# SCH_OpenRICE.net
KiCad netlist of a schematic drawn in EasyEDA
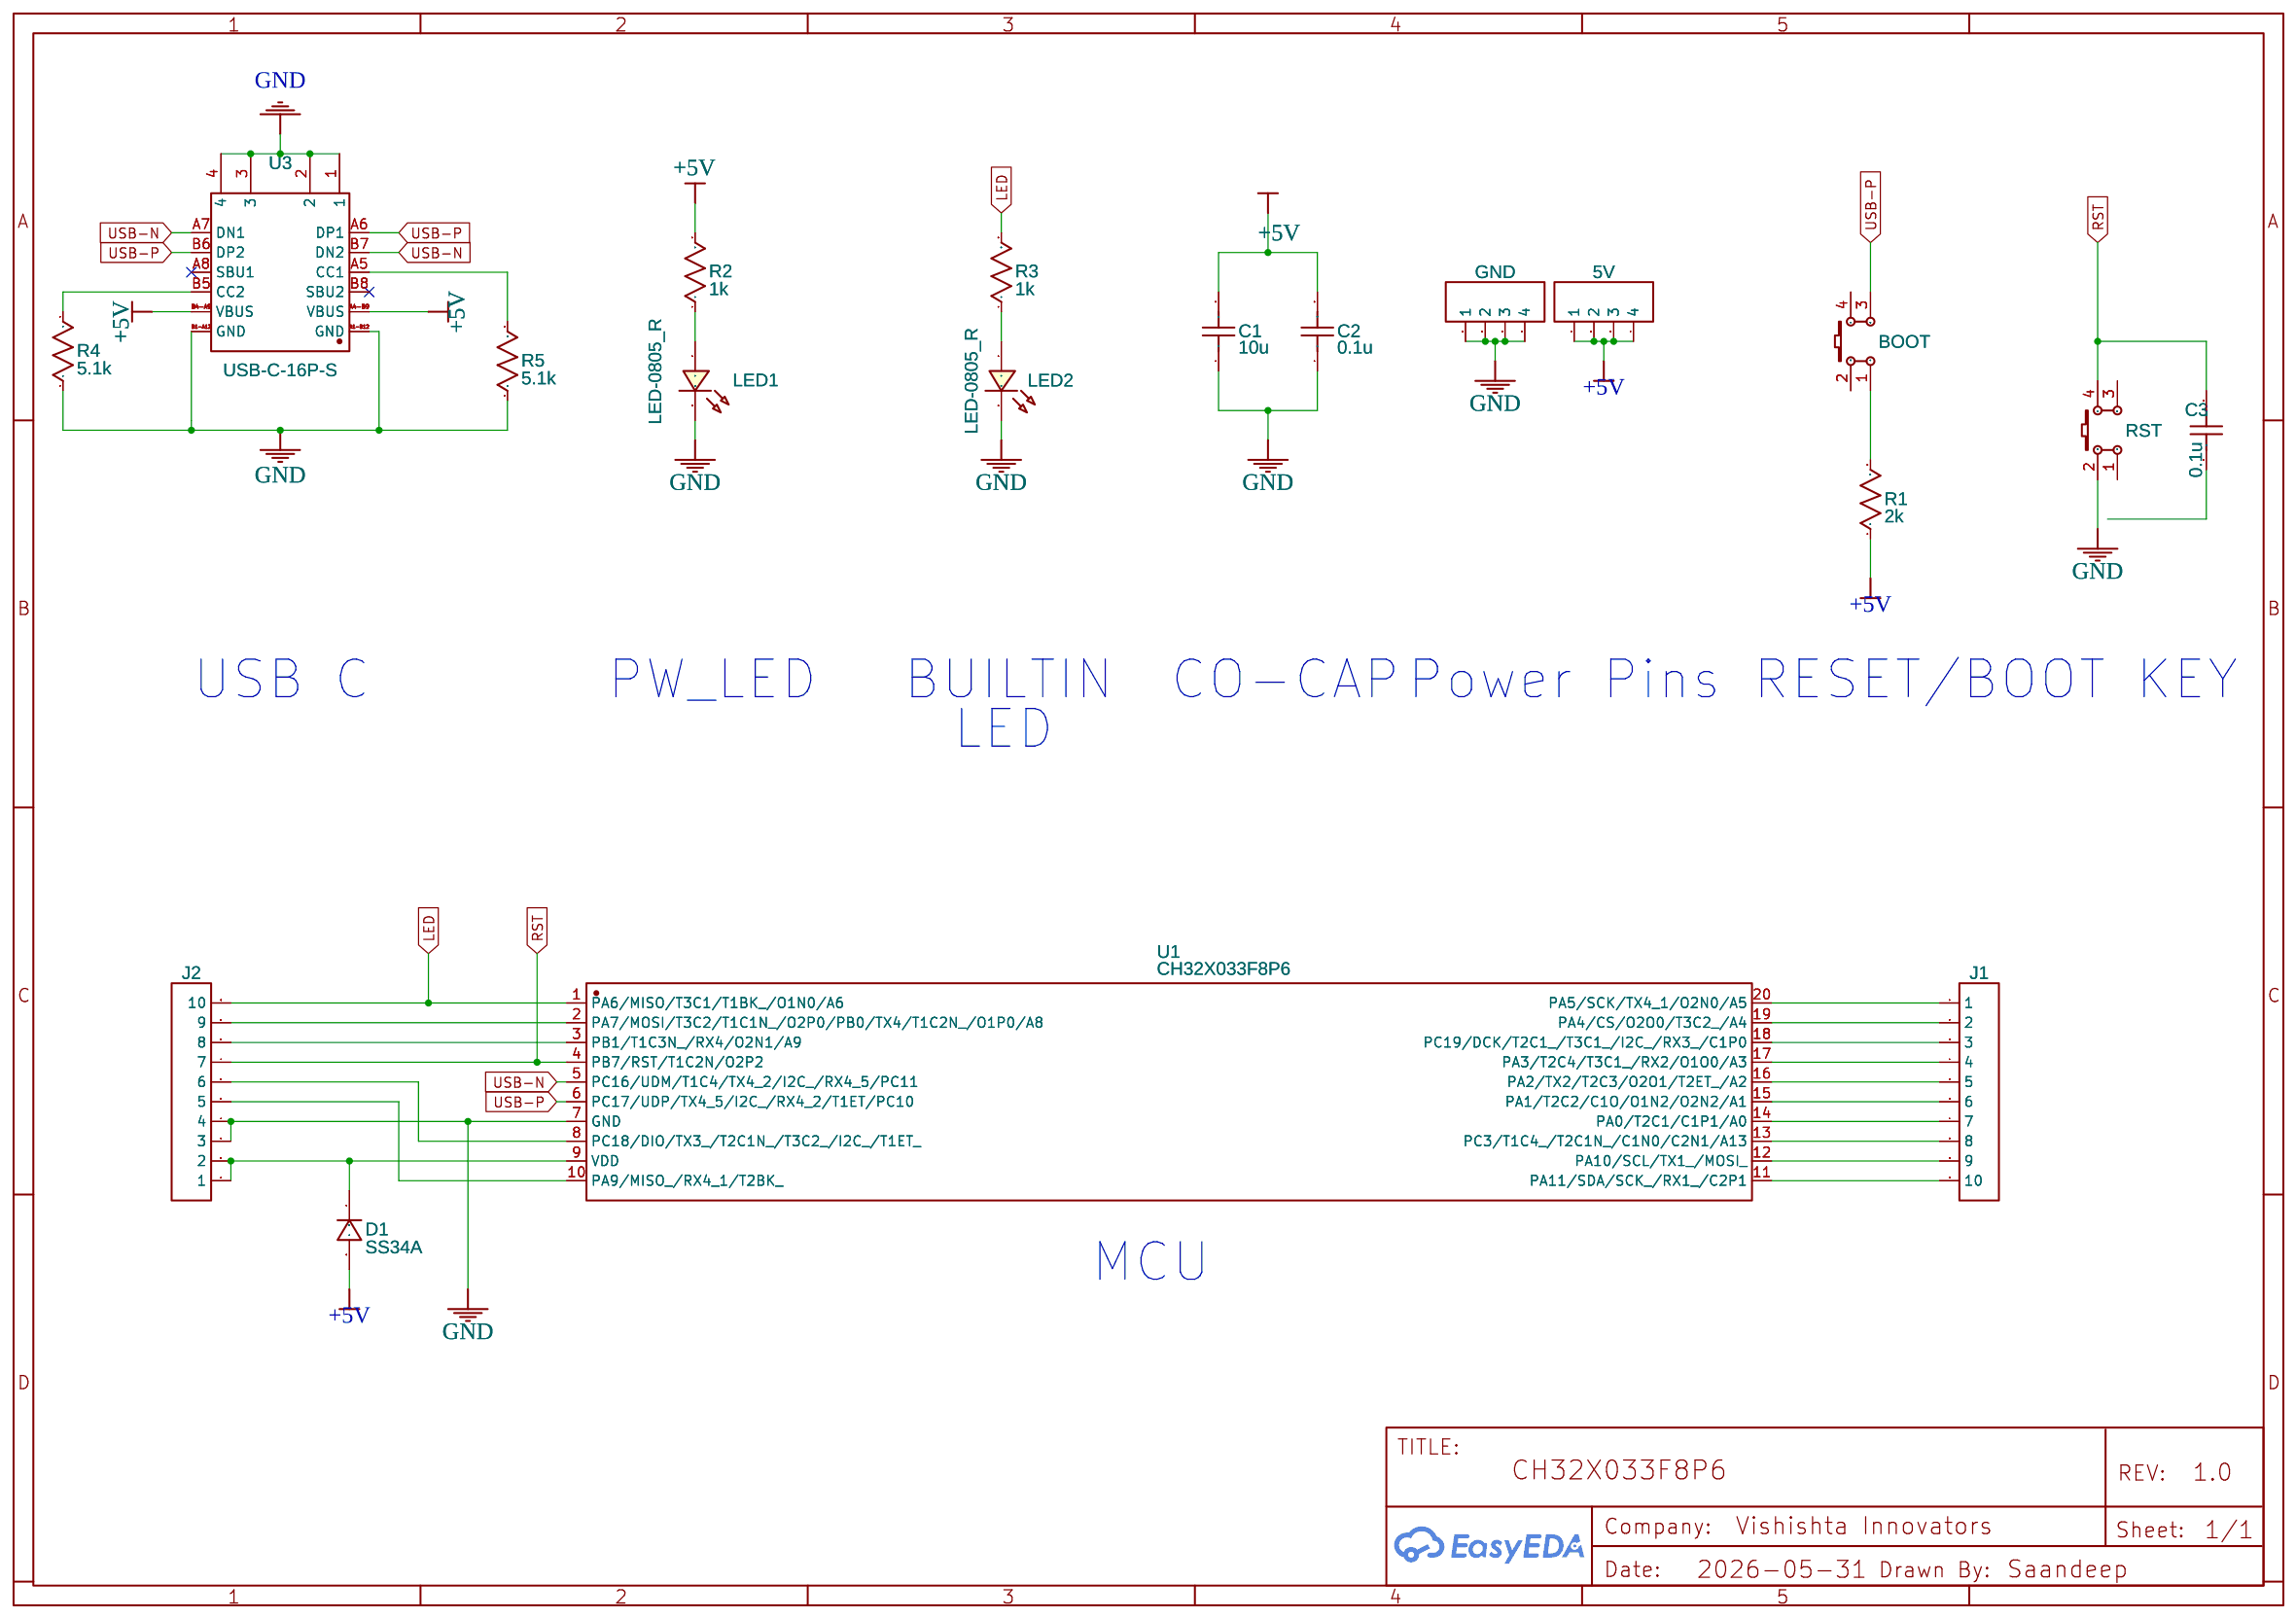
[diagram p0: schematic sheet]

(export (version "E")
  (design (tool "Eeschema 10.0.6"))
  (components
    (comp (ref "5V") (value "HDR-M-2.54_1x4") (libsource (lib "") (part "HDR-M-2.54_1x4")))
    (comp (ref "BOOT")
      (value "K4-6×6_TH")
      (fields (field (name "Manufacturer Part") "K2-1102DP-E4SW-04") (field (name "Manufacturer") "韩国韩荣"))
      (libsource (lib "") (part "K4-6×6_TH_1"))
    )
    (comp (ref "C1") (value "10u") (libsource (lib "") (part "C_0805_US")))
    (comp (ref "C2") (value "0.1u") (libsource (lib "") (part "C_0805_US")))
    (comp (ref "C3") (value "0.1u") (libsource (lib "") (part "C_0805_US")))
    (comp (ref "D1")
      (value "SS34A")
      (fields (field (name "Manufacturer") "YANGJIE(扬杰)"))
      (libsource (lib "") (part "SS34A"))
    )
    (comp (ref "GND") (value "HDR-M-2.54_1x4") (libsource (lib "") (part "HDR-M-2.54_1x4_1")))
    (comp (ref "J1") (value "HDR-M-2.54_1x10") (libsource (lib "") (part "HDR-M-2.54_1x10")))
    (comp (ref "J2") (value "HDR-M-2.54_1x10") (libsource (lib "") (part "HDR-M-2.54_1x10_1")))
    (comp (ref "LED1")
      (value "LED-0805_R")
      (fields
        (field (name "Manufacturer Part") "17-21SURC/S530-A3/TR8")
        (field (name "Manufacturer") "EVERLIGHT(台湾亿光)")
      )
      (libsource (lib "") (part "LED-0805_R"))
    )
    (comp (ref "LED2")
      (value "LED-0805_R")
      (fields
        (field (name "Manufacturer Part") "17-21SURC/S530-A3/TR8")
        (field (name "Manufacturer") "EVERLIGHT(台湾亿光)")
      )
      (libsource (lib "") (part "LED-0805_R"))
    )
    (comp (ref "R1") (value "2k") (libsource (lib "") (part "R_0805_US")))
    (comp (ref "R2") (value "1k") (libsource (lib "") (part "R_0805_US")))
    (comp (ref "R3") (value "1k") (libsource (lib "") (part "R_0805_US")))
    (comp (ref "R4") (value "5.1k") (libsource (lib "") (part "R_0805_US")))
    (comp (ref "R5") (value "5.1k") (libsource (lib "") (part "R_0805_US")))
    (comp (ref "RST")
      (value "K4-6×6_TH")
      (fields (field (name "Manufacturer Part") "K2-1102DP-E4SW-04") (field (name "Manufacturer") "韩国韩荣"))
      (libsource (lib "") (part "K4-6×6_TH"))
    )
    (comp (ref "U1")
      (value "CH32X033F8P6")
      (fields (field (name "Manufacturer") "WCH(南京沁恒)"))
      (libsource (lib "") (part "CH32X033F8P6"))
    )
    (comp (ref "U3") (value "USB-C-16P-S") (libsource (lib "") (part "USB-C-16P-S")))
  )
  (nets
    (net (code "1") (name "+5V") (class "Default")
      (node (ref "5V") (pin "1") (pinfunction "1_1") (pintype "unspecified"))
      (node (ref "5V") (pin "2") (pinfunction "2_2") (pintype "unspecified"))
      (node (ref "5V") (pin "3") (pinfunction "3_3") (pintype "unspecified"))
      (node (ref "5V") (pin "4") (pinfunction "4_4") (pintype "unspecified"))
      (node (ref "C1") (pin "2") (pinfunction "2_2") (pintype "unspecified"))
      (node (ref "C2") (pin "2") (pinfunction "2_2") (pintype "unspecified"))
      (node (ref "D1") (pin "2") (pinfunction "A_2") (pintype "unspecified"))
      (node (ref "R1") (pin "1") (pinfunction "1_1") (pintype "unspecified"))
      (node (ref "R2") (pin "2") (pinfunction "2_2") (pintype "unspecified"))
      (node (ref "U3") (pin "A4-B9") (pinfunction "VBUS_A4-B9") (pintype "unspecified"))
      (node (ref "U3") (pin "B4-A9") (pinfunction "VBUS_B4-A9") (pintype "unspecified"))
    )
    (net (code "2") (name "GND") (class "Default")
      (node (ref "C1") (pin "1") (pinfunction "1_1") (pintype "unspecified"))
      (node (ref "C2") (pin "1") (pinfunction "1_1") (pintype "unspecified"))
      (node (ref "GND") (pin "1") (pinfunction "1_1") (pintype "unspecified"))
      (node (ref "GND") (pin "2") (pinfunction "2_2") (pintype "unspecified"))
      (node (ref "GND") (pin "3") (pinfunction "3_3") (pintype "unspecified"))
      (node (ref "GND") (pin "4") (pinfunction "4_4") (pintype "unspecified"))
      (node (ref "J2") (pin "3") (pinfunction "3_3") (pintype "unspecified"))
      (node (ref "J2") (pin "4") (pinfunction "4_4") (pintype "unspecified"))
      (node (ref "LED1") (pin "2") (pinfunction "2_2") (pintype "unspecified"))
      (node (ref "LED2") (pin "2") (pinfunction "2_2") (pintype "unspecified"))
      (node (ref "R4") (pin "1") (pinfunction "1_1") (pintype "unspecified"))
      (node (ref "R5") (pin "1") (pinfunction "1_1") (pintype "unspecified"))
      (node (ref "RST") (pin "2") (pinfunction "2_2") (pintype "unspecified"))
      (node (ref "U1") (pin "7") (pinfunction "GND_7") (pintype "unspecified"))
      (node (ref "U3") (pin "1") (pinfunction "1_1") (pintype "unspecified"))
      (node (ref "U3") (pin "2") (pinfunction "2_2") (pintype "unspecified"))
      (node (ref "U3") (pin "3") (pinfunction "3_3") (pintype "unspecified"))
      (node (ref "U3") (pin "4") (pinfunction "4_4") (pintype "unspecified"))
      (node (ref "U3") (pin "A1-B12") (pinfunction "GND_A1-B12") (pintype "unspecified"))
      (node (ref "U3") (pin "B1-A12") (pinfunction "GND_B1-A12") (pintype "unspecified"))
    )
    (net (code "3") (name "LED") (class "Default")
      (node (ref "J2") (pin "10") (pinfunction "10_10") (pintype "unspecified"))
      (node (ref "R3") (pin "2") (pinfunction "2_2") (pintype "unspecified"))
      (node (ref "U1") (pin "1") (pinfunction "PA6/MISO/T3C1/T1BK_/O1N0/A6_1") (pintype "unspecified"))
    )
    (net (code "4") (name "Net-(BOOT-Pad1)") (class "Default")
      (node (ref "BOOT") (pin "1") (pinfunction "1_1") (pintype "unspecified"))
      (node (ref "R1") (pin "2") (pinfunction "2_2") (pintype "unspecified"))
    )
    (net (code "5") (name "Net-(D1-C)") (class "Default")
      (node (ref "D1") (pin "1") (pinfunction "C_1") (pintype "unspecified"))
      (node (ref "J2") (pin "1") (pinfunction "1_1") (pintype "unspecified"))
      (node (ref "J2") (pin "2") (pinfunction "2_2") (pintype "unspecified"))
      (node (ref "U1") (pin "9") (pinfunction "VDD_9") (pintype "unspecified"))
    )
    (net (code "6") (name "Net-(LED1-Pad1)") (class "Default")
      (node (ref "LED1") (pin "1") (pinfunction "1_1") (pintype "unspecified"))
      (node (ref "R2") (pin "1") (pinfunction "1_1") (pintype "unspecified"))
    )
    (net (code "7") (name "Net-(LED2-Pad1)") (class "Default")
      (node (ref "LED2") (pin "1") (pinfunction "1_1") (pintype "unspecified"))
      (node (ref "R3") (pin "1") (pinfunction "1_1") (pintype "unspecified"))
    )
    (net (code "8") (name "Net-(U1-PA0{slash}T2C1{slash}C1P1{slash}A0)") (class "Default")
      (node (ref "J1") (pin "7") (pinfunction "7_7") (pintype "unspecified"))
      (node (ref "U1") (pin "14") (pinfunction "PA0/T2C1/C1P1/A0_14") (pintype "unspecified"))
    )
    (net (code "9") (name "Net-(U1-PA1{slash}T2C2{slash}C1O{slash}O1N2{slash}O2N2{slash}A1)") (class "Default")
      (node (ref "J1") (pin "6") (pinfunction "6_6") (pintype "unspecified"))
      (node (ref "U1") (pin "15") (pinfunction "PA1/T2C2/C1O/O1N2/O2N2/A1_15") (pintype "unspecified"))
    )
    (net (code "10") (name "Net-(U1-PA2{slash}TX2{slash}T2C3{slash}O2O1{slash}T2ET_{slash}A2)") (class "Default")
      (node (ref "J1") (pin "5") (pinfunction "5_5") (pintype "unspecified"))
      (node (ref "U1") (pin "16") (pinfunction "PA2/TX2/T2C3/O2O1/T2ET_/A2_16") (pintype "unspecified"))
    )
    (net (code "11") (name "Net-(U1-PA3{slash}T2C4{slash}T3C1_{slash}RX2{slash}O1O0{slash}A3)") (class "Default")
      (node (ref "J1") (pin "4") (pinfunction "4_4") (pintype "unspecified"))
      (node (ref "U1") (pin "17") (pinfunction "PA3/T2C4/T3C1_/RX2/O1O0/A3_17") (pintype "unspecified"))
    )
    (net (code "12") (name "Net-(U1-PA4{slash}CS{slash}O2O0{slash}T3C2_{slash}A4)") (class "Default")
      (node (ref "J1") (pin "2") (pinfunction "2_2") (pintype "unspecified"))
      (node (ref "U1") (pin "19") (pinfunction "PA4/CS/O2O0/T3C2_/A4_19") (pintype "unspecified"))
    )
    (net (code "13") (name "Net-(U1-PA5{slash}SCK{slash}TX4_1{slash}O2N0{slash}A5)") (class "Default")
      (node (ref "J1") (pin "1") (pinfunction "1_1") (pintype "unspecified"))
      (node (ref "U1") (pin "20") (pinfunction "PA5/SCK/TX4_1/O2N0/A5_20") (pintype "unspecified"))
    )
    (net (code "14") (name "Net-(U1-PA7{slash}MOSI{slash}T3C2{slash}T1C1N_{slash}O2P0{slash}PB0{slash}TX4{slash}T1C2N_{slash}O1P0{slash}A8)") (class "Default")
      (node (ref "J2") (pin "9") (pinfunction "9_9") (pintype "unspecified"))
      (node (ref "U1") (pin "2") (pinfunction "PA7/MOSI/T3C2/T1C1N_/O2P0/PB0/TX4/T1C2N_/O1P0/A8_2") (pintype "unspecified"))
    )
    (net (code "15") (name "Net-(U1-PA9{slash}MISO_{slash}RX4_1{slash}T2BK_)") (class "Default")
      (node (ref "J2") (pin "5") (pinfunction "5_5") (pintype "unspecified"))
      (node (ref "U1") (pin "10") (pinfunction "PA9/MISO_/RX4_1/T2BK__10") (pintype "unspecified"))
    )
    (net (code "16") (name "Net-(U1-PA10{slash}SCL{slash}TX1_{slash}MOSI_)") (class "Default")
      (node (ref "J1") (pin "9") (pinfunction "9_9") (pintype "unspecified"))
      (node (ref "U1") (pin "12") (pinfunction "PA10/SCL/TX1_/MOSI__12") (pintype "unspecified"))
    )
    (net (code "17") (name "Net-(U1-PA11{slash}SDA{slash}SCK_{slash}RX1_{slash}C2P1)") (class "Default")
      (node (ref "J1") (pin "10") (pinfunction "10_10") (pintype "unspecified"))
      (node (ref "U1") (pin "11") (pinfunction "PA11/SDA/SCK_/RX1_/C2P1_11") (pintype "unspecified"))
    )
    (net (code "18") (name "Net-(U1-PB1{slash}T1C3N_{slash}RX4{slash}O2N1{slash}A9)") (class "Default")
      (node (ref "J2") (pin "8") (pinfunction "8_8") (pintype "unspecified"))
      (node (ref "U1") (pin "3") (pinfunction "PB1/T1C3N_/RX4/O2N1/A9_3") (pintype "unspecified"))
    )
    (net (code "19") (name "Net-(U1-PC3{slash}T1C4_{slash}T2C1N_{slash}C1N0{slash}C2N1{slash}A13)") (class "Default")
      (node (ref "J1") (pin "8") (pinfunction "8_8") (pintype "unspecified"))
      (node (ref "U1") (pin "13") (pinfunction "PC3/T1C4_/T2C1N_/C1N0/C2N1/A13_13") (pintype "unspecified"))
    )
    (net (code "20") (name "Net-(U1-PC18{slash}DIO{slash}TX3_{slash}T2C1N_{slash}T3C2_{slash}I2C_{slash}T1ET_)") (class "Default")
      (node (ref "J2") (pin "6") (pinfunction "6_6") (pintype "unspecified"))
      (node (ref "U1") (pin "8") (pinfunction "PC18/DIO/TX3_/T2C1N_/T3C2_/I2C_/T1ET__8") (pintype "unspecified"))
    )
    (net (code "21") (name "Net-(U1-PC19{slash}DCK{slash}T2C1_{slash}T3C1_{slash}I2C_{slash}RX3_{slash}C1P0)") (class "Default")
      (node (ref "J1") (pin "3") (pinfunction "3_3") (pintype "unspecified"))
      (node (ref "U1") (pin "18") (pinfunction "PC19/DCK/T2C1_/T3C1_/I2C_/RX3_/C1P0_18") (pintype "unspecified"))
    )
    (net (code "22") (name "Net-(U3-CC1)") (class "Default")
      (node (ref "R5") (pin "2") (pinfunction "2_2") (pintype "unspecified"))
      (node (ref "U3") (pin "A5") (pinfunction "CC1_A5") (pintype "unspecified"))
    )
    (net (code "23") (name "Net-(U3-CC2)") (class "Default")
      (node (ref "R4") (pin "2") (pinfunction "2_2") (pintype "unspecified"))
      (node (ref "U3") (pin "B5") (pinfunction "CC2_B5") (pintype "unspecified"))
    )
    (net (code "24") (name "RST") (class "Default")
      (node (ref "C3") (pin "2") (pinfunction "2_2") (pintype "unspecified"))
      (node (ref "J2") (pin "7") (pinfunction "7_7") (pintype "unspecified"))
      (node (ref "RST") (pin "4") (pinfunction "4_4") (pintype "unspecified"))
      (node (ref "U1") (pin "4") (pinfunction "PB7/RST/T1C2N/O2P2_4") (pintype "unspecified"))
    )
    (net (code "25") (name "USB-N") (class "Default")
      (node (ref "U1") (pin "5") (pinfunction "PC16/UDM/T1C4/TX4_2/I2C_/RX4_5/PC11_5") (pintype "unspecified"))
      (node (ref "U3") (pin "A7") (pinfunction "DN1_A7") (pintype "unspecified"))
      (node (ref "U3") (pin "B7") (pinfunction "DN2_B7") (pintype "unspecified"))
    )
    (net (code "26") (name "USB-P") (class "Default")
      (node (ref "BOOT") (pin "3") (pinfunction "3_3") (pintype "unspecified"))
      (node (ref "U1") (pin "6") (pinfunction "PC17/UDP/TX4_5/I2C_/RX4_2/T1ET/PC10_6") (pintype "unspecified"))
      (node (ref "U3") (pin "A6") (pinfunction "DP1_A6") (pintype "unspecified"))
      (node (ref "U3") (pin "B6") (pinfunction "DP2_B6") (pintype "unspecified"))
    )
    (net (code "27") (name "unconnected-(BOOT-Pad2)") (class "Default")
      (node (ref "BOOT") (pin "2") (pinfunction "2_2") (pintype "unspecified"))
    )
    (net (code "28") (name "unconnected-(BOOT-Pad4)") (class "Default")
      (node (ref "BOOT") (pin "4") (pinfunction "4_4") (pintype "unspecified"))
    )
    (net (code "29") (name "unconnected-(C3-Pad1)") (class "Default")
      (node (ref "C3") (pin "1") (pinfunction "1_1") (pintype "unspecified"))
    )
    (net (code "30") (name "unconnected-(RST-Pad1)") (class "Default")
      (node (ref "RST") (pin "1") (pinfunction "1_1") (pintype "unspecified"))
    )
    (net (code "31") (name "unconnected-(RST-Pad3)") (class "Default")
      (node (ref "RST") (pin "3") (pinfunction "3_3") (pintype "unspecified"))
    )
    (net (code "32") (name "unconnected-(U3-SBU1-PadA8)") (class "Default")
      (node (ref "U3") (pin "A8") (pinfunction "SBU1_A8") (pintype "unspecified+no_connect"))
    )
    (net (code "33") (name "unconnected-(U3-SBU2-PadB8)") (class "Default")
      (node (ref "U3") (pin "B8") (pinfunction "SBU2_B8") (pintype "unspecified+no_connect"))
    )
  )
)
